# Precharge.net
KiCad netlist of a schematic drawn in Altium Designer
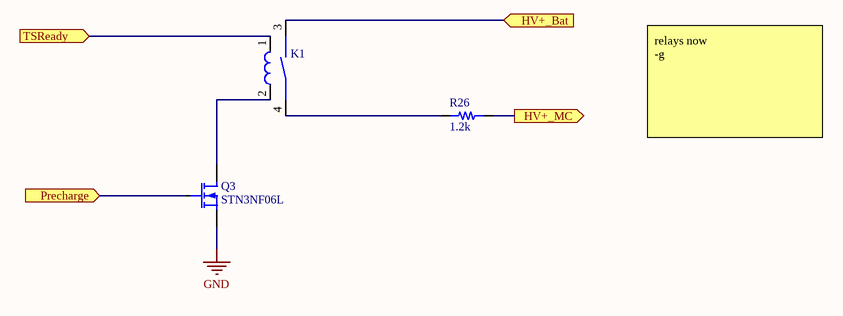
[diagram p0: Precharge.SchDoc]

(export (version "E")
  (design (tool "Eeschema 10.0.6"))
  (components
    (comp (ref "K1")
      (value "LI24-1A85")
      (footprint "LI24-1A85")
      (description "RELAY REED SPST 1A 24V")
      (fields (field (name "VOLTAGE") "12") (field (name "CREATEDBY") "gray"))
      (libsource (lib "altlib") (part "LI24-1A85"))
    )
    (comp (ref "Q3")
      (value "STN3NF06L")
      (footprint "STN3NF06L")
      (description "MOSFET N-CH 60V 4A SOT223")
      (libsource (lib "altlib") (part "STN3NF06L"))
    )
    (comp (ref "R26")
      (value "1.2k")
      (footprint "AP101")
      (description "100W Throughhole Resistor")
      (fields
        (field (name "TOLERANCE") "5%")
        (field (name "POWER") "100W")
        (field (name "CREATED_BY") "Graydon")
      )
      (libsource (lib "Altium-Lib") (part "Resistor"))
    )
  )
  (nets
    (net (code "1") (name "/HV+_Bat") (class "Default")
      (node (ref "K1") (pin "3") (pinfunction "3_3") (pintype "passive"))
    )
    (net (code "2") (name "/HV+_MC") (class "Default")
      (node (ref "R26") (pin "2") (pinfunction "2_2") (pintype "passive"))
    )
    (net (code "3") (name "/Precharge") (class "Default")
      (node (ref "Q3") (pin "1") (pinfunction "G_1") (pintype "passive"))
    )
    (net (code "4") (name "/TSReady") (class "Default")
      (node (ref "K1") (pin "1") (pinfunction "0_1") (pintype "passive"))
    )
    (net (code "5") (name "GND") (class "Default")
      (node (ref "Q3") (pin "3") (pinfunction "S_3") (pintype "passive"))
    )
    (net (code "6") (name "Net-(K1-1)") (class "Default")
      (node (ref "K1") (pin "2") (pinfunction "1_2") (pintype "passive"))
      (node (ref "Q3") (pin "2") (pinfunction "D_2") (pintype "passive"))
    )
    (net (code "7") (name "Net-(K1-Pad4)") (class "Default")
      (node (ref "K1") (pin "4") (pinfunction "4_4") (pintype "passive"))
      (node (ref "R26") (pin "1") (pinfunction "1_1") (pintype "passive"))
    )
  )
)
